# TransducerStuff.net
KiCad netlist of a schematic drawn in EAGLE
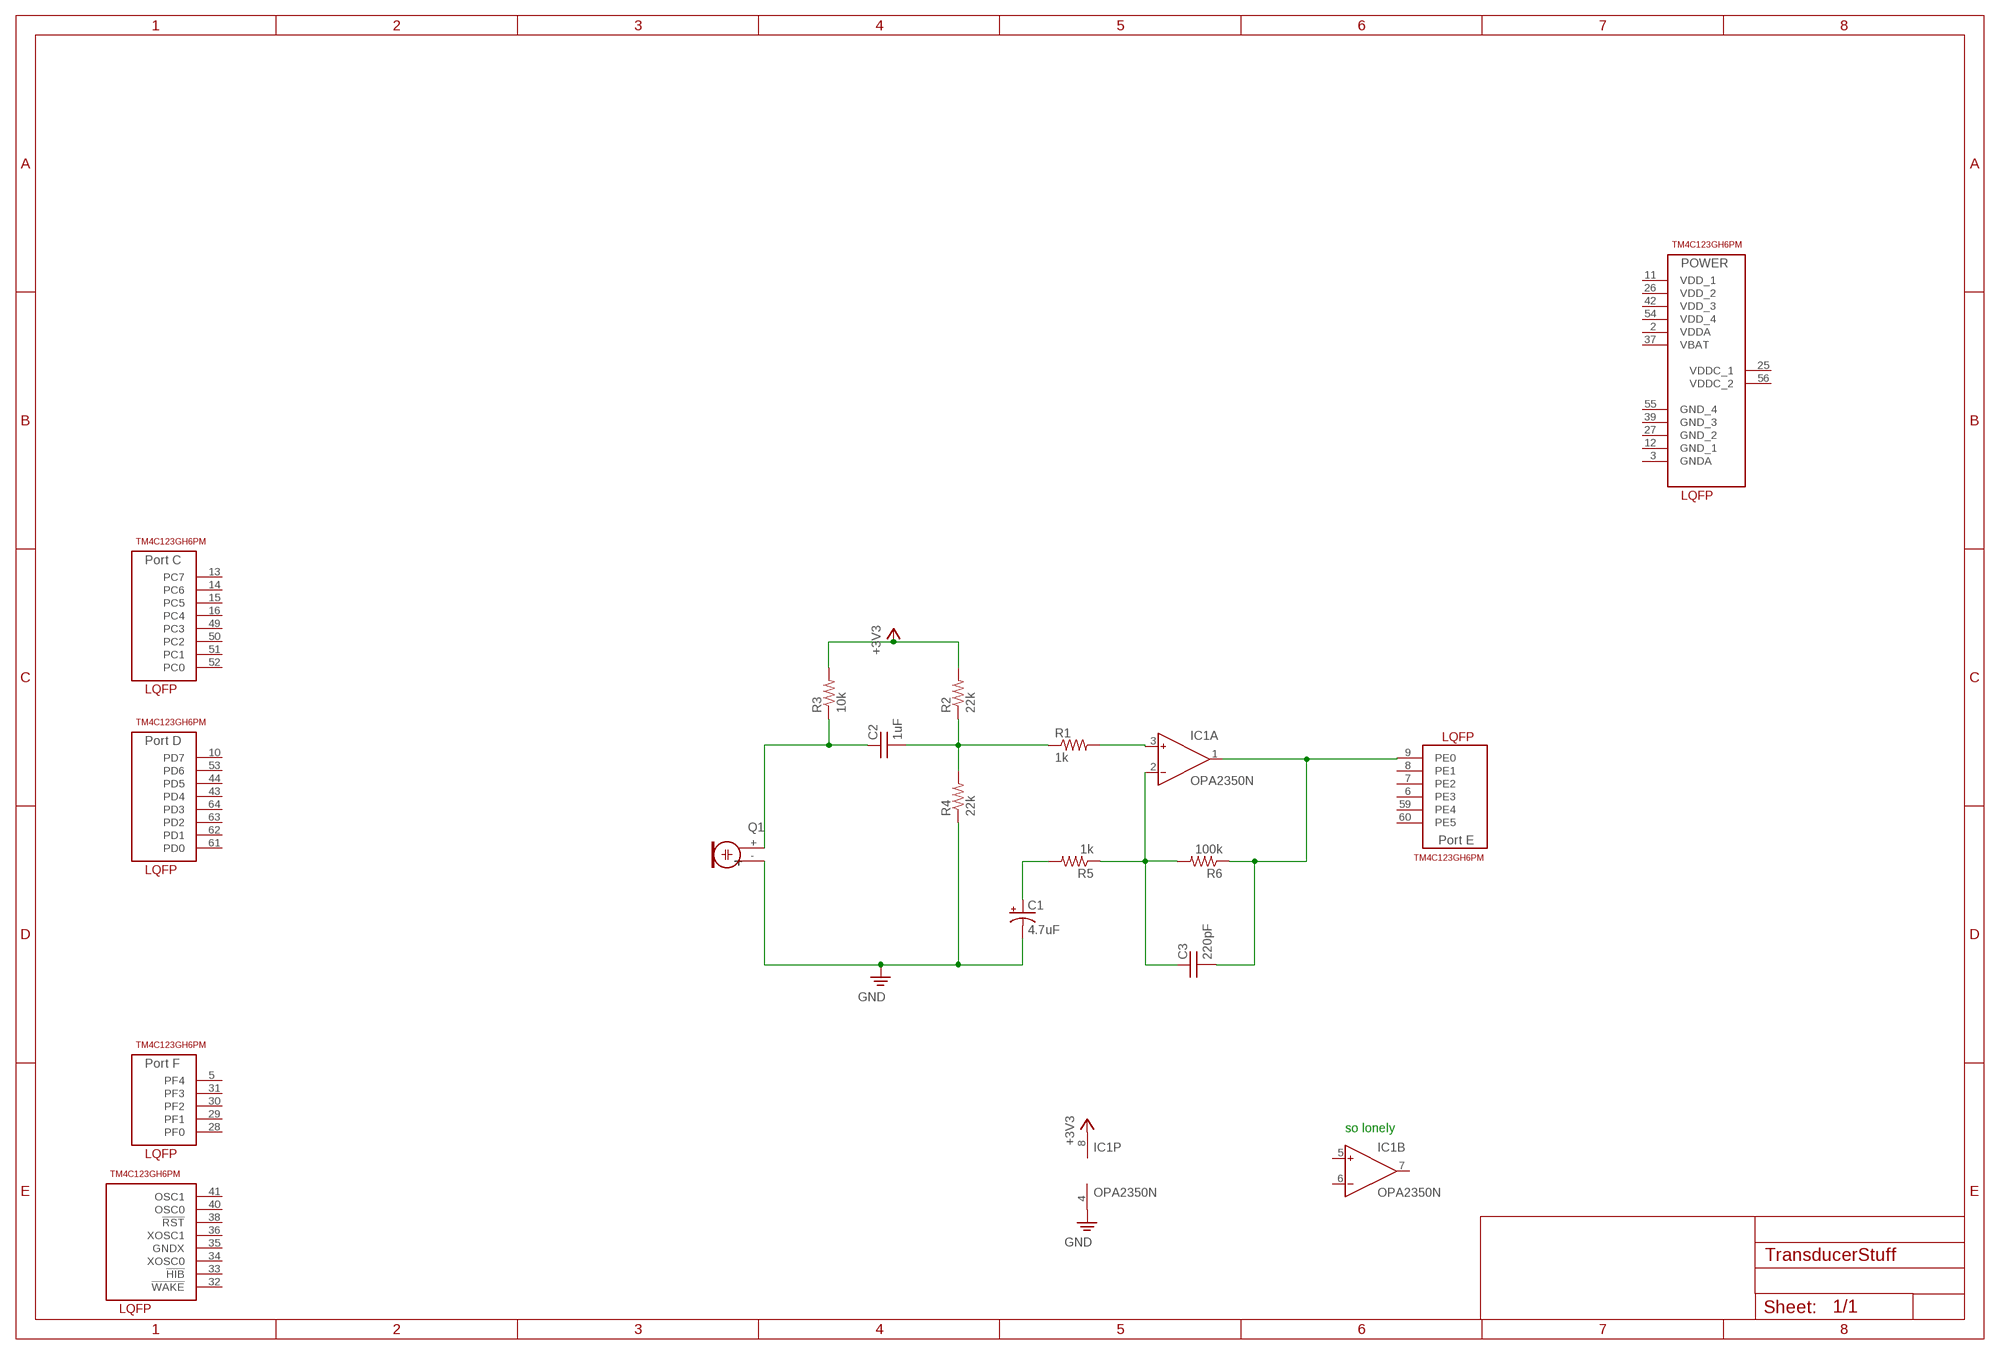
[diagram p0: schematic, sheet 1, part 1 of 2]
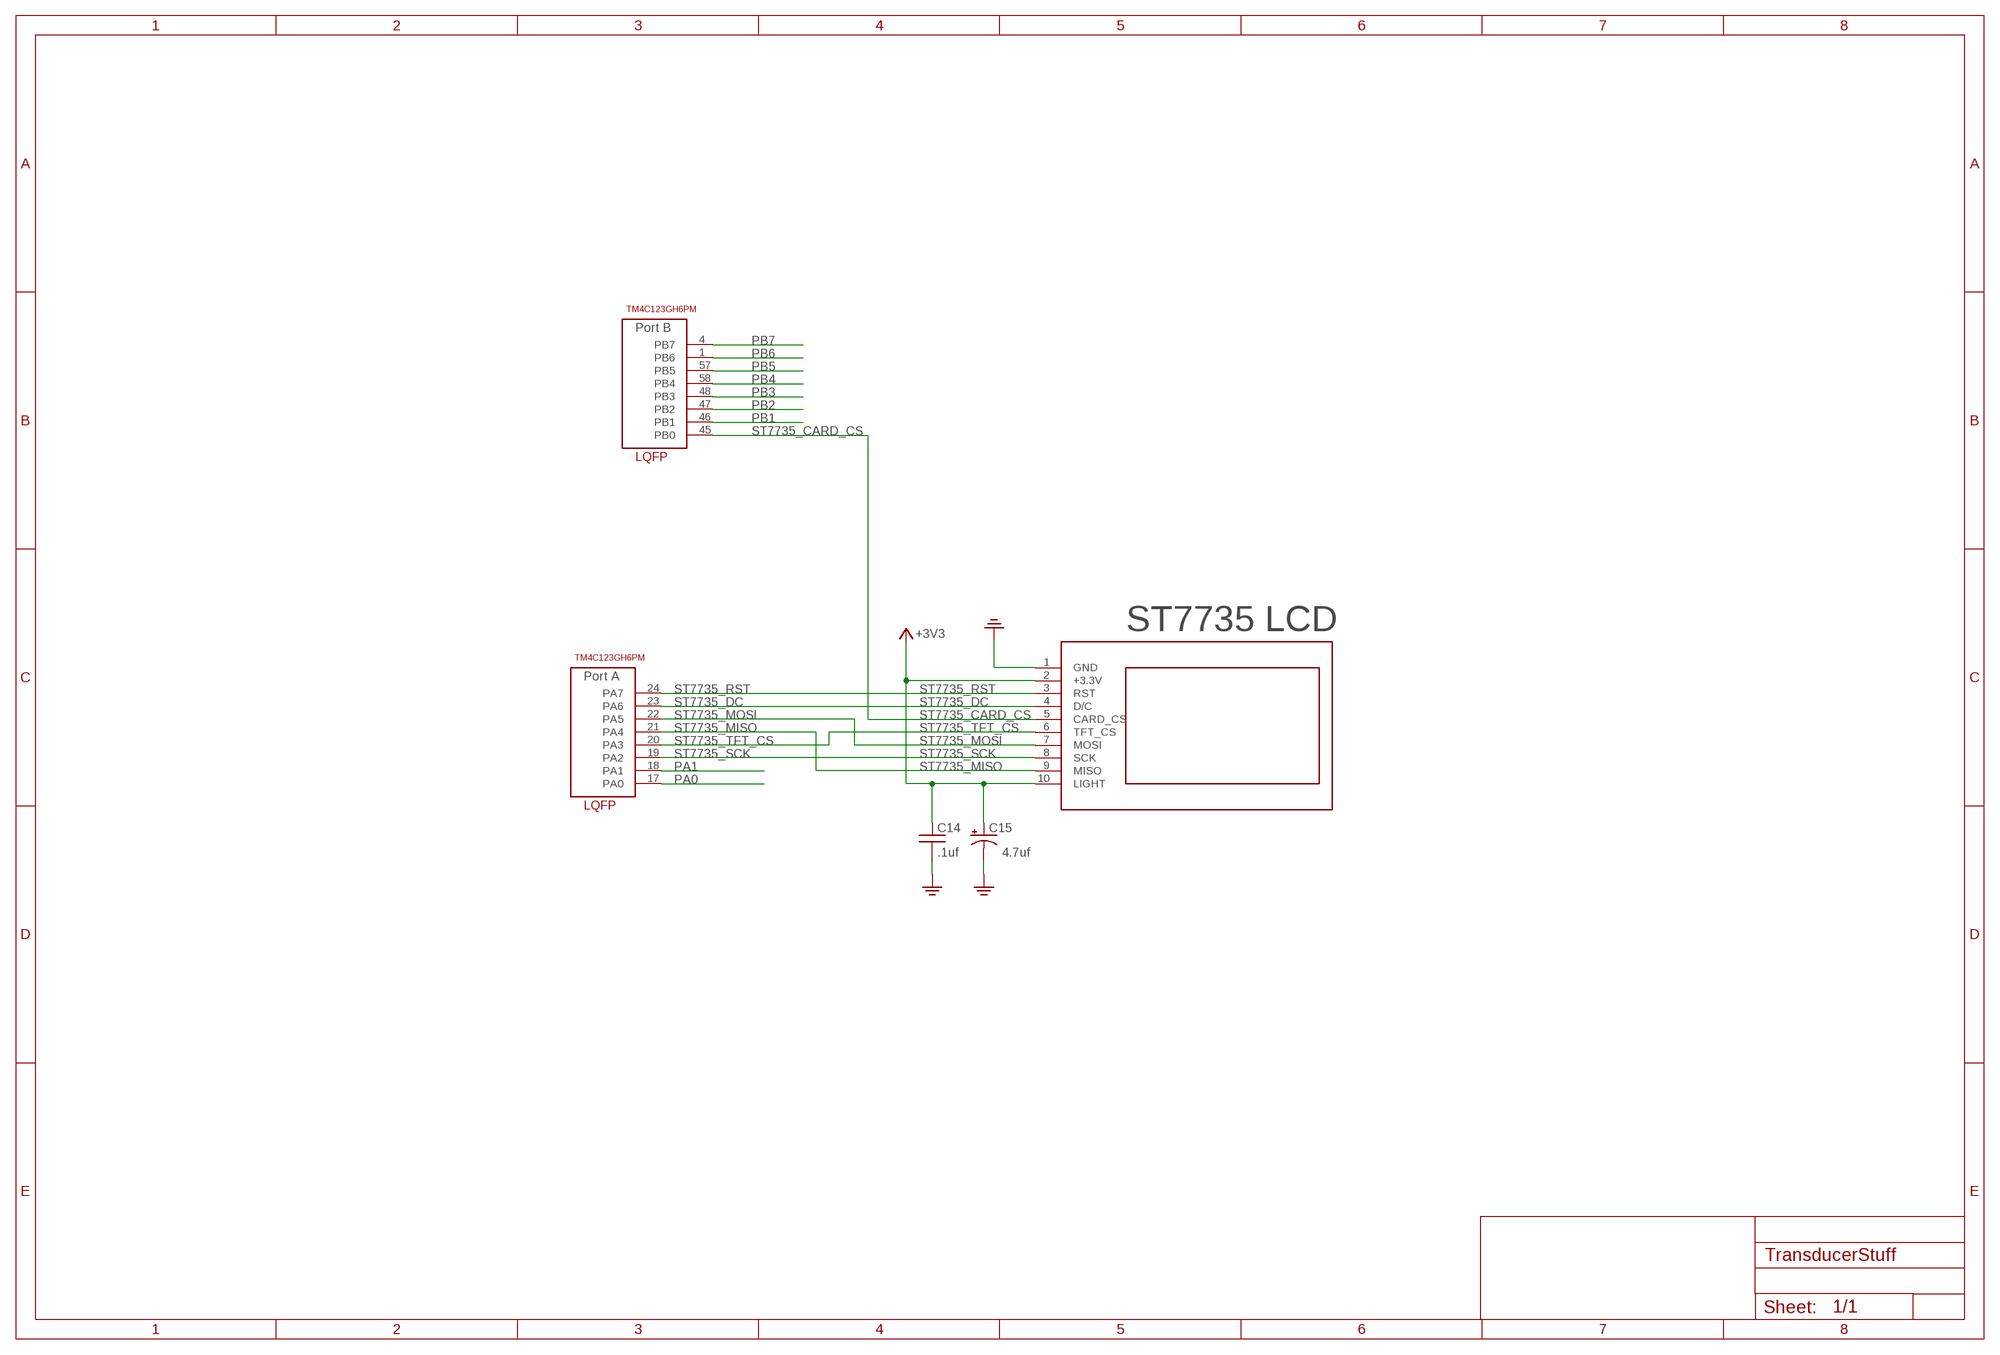
[diagram p1: schematic, sheet 1, part 2 of 2]

(export (version "E")
  (design (tool "Eeschema 10.0.6"))
  (components
    (comp (ref "C1")
      (value "4.7uF")
      (footprint "eagle-import:CAP200MILPOLARIZED")
      (libsource (lib "eagle-import") (part "CAPACITOR_POLARIZEDE5-6"))
    )
    (comp (ref "C2")
      (value "1uF")
      (footprint "eagle-import:CAP200MIL")
      (libsource (lib "eagle-import") (part "CAPACITOR050-024X044"))
    )
    (comp (ref "C3")
      (value "220pF")
      (footprint "eagle-import:CAP200MIL")
      (libsource (lib "eagle-import") (part "CAPACITOR050-024X044"))
    )
    (comp (ref "C14")
      (value ".1uf")
      (footprint "eagle-import:CAP200MIL")
      (libsource (lib "eagle-import") (part "CAPACITOR050-024X044"))
    )
    (comp (ref "C15")
      (value "4.7uf")
      (footprint "eagle-import:CAP200MILPOLARIZED")
      (libsource (lib "eagle-import") (part "CAPACITOR_POLARIZEDE5-6"))
    )
    (comp (ref "IC1")
      (value "OPA2350N")
      (footprint "eagle-import:DIL08")
      (libsource (lib "eagle-import") (part "OPA2350N"))
    )
    (comp (ref "Q1")
      (value "ELECTRET")
      (footprint "eagle-import:9.7ELECTRET")
      (libsource (lib "eagle-import") (part "ELECTRET"))
    )
    (comp (ref "R1")
      (value "1k")
      (footprint "eagle-import:RES400MIL")
      (libsource (lib "eagle-import") (part "RESISTOR0309/10"))
    )
    (comp (ref "R2")
      (value "22k")
      (footprint "eagle-import:RES400MIL")
      (libsource (lib "eagle-import") (part "RESISTOR0309/10"))
    )
    (comp (ref "R3")
      (value "10k")
      (footprint "eagle-import:RES400MIL")
      (libsource (lib "eagle-import") (part "RESISTOR0309/10"))
    )
    (comp (ref "R4")
      (value "22k")
      (footprint "eagle-import:RES400MIL")
      (libsource (lib "eagle-import") (part "RESISTOR0309/10"))
    )
    (comp (ref "R5")
      (value "1k")
      (footprint "eagle-import:RES400MIL")
      (libsource (lib "eagle-import") (part "RESISTOR0309/10"))
    )
    (comp (ref "R6")
      (value "100k")
      (footprint "eagle-import:RES400MIL")
      (libsource (lib "eagle-import") (part "RESISTOR0309/10"))
    )
    (comp (ref "U$1")
      (value "TM4C123GH6PM")
      (footprint "eagle-import:QFP50P1200X1200X160-64N")
      (libsource (lib "eagle-import") (part "TM4C123GH6PM"))
    )
    (comp (ref "U$2")
      (value "TM4C123GH6PM")
      (footprint "eagle-import:QFP50P1200X1200X160-64N")
      (libsource (lib "eagle-import") (part "TM4C123GH6PM"))
    )
    (comp (ref "U$3")
      (value "TM4C123GH6PM")
      (footprint "eagle-import:QFP50P1200X1200X160-64N")
      (libsource (lib "eagle-import") (part "TM4C123GH6PM"))
    )
    (comp (ref "U$4")
      (value "TM4C123GH6PM")
      (footprint "eagle-import:QFP50P1200X1200X160-64N")
      (libsource (lib "eagle-import") (part "TM4C123GH6PM"))
    )
    (comp (ref "U$5")
      (value "TM4C123GH6PM")
      (footprint "eagle-import:QFP50P1200X1200X160-64N")
      (libsource (lib "eagle-import") (part "TM4C123GH6PM"))
    )
    (comp (ref "U$6")
      (value "TM4C123GH6PM")
      (footprint "eagle-import:QFP50P1200X1200X160-64N")
      (libsource (lib "eagle-import") (part "TM4C123GH6PM"))
    )
    (comp (ref "U$7")
      (value "TM4C123GH6PM")
      (footprint "eagle-import:QFP50P1200X1200X160-64N")
      (libsource (lib "eagle-import") (part "TM4C123GH6PM"))
    )
    (comp (ref "U$8")
      (value "TM4C123GH6PM")
      (footprint "eagle-import:QFP50P1200X1200X160-64N")
      (libsource (lib "eagle-import") (part "TM4C123GH6PM"))
    )
    (comp (ref "U$10")
      (value "ST7735")
      (footprint "eagle-import:ST7735")
      (libsource (lib "eagle-import") (part "ST7735"))
    )
  )
  (nets
    (net (code "1") (name "+3V3") (class "Default")
      (node (ref "C14") (pin "1") (pinfunction "1_1") (pintype "passive"))
      (node (ref "C15") (pin "+") (pinfunction "+_+") (pintype "passive"))
      (node (ref "IC1") (pin "8") (pinfunction "V+_8") (pintype "power_in"))
      (node (ref "R2") (pin "2") (pinfunction "2_2") (pintype "passive"))
      (node (ref "R3") (pin "2") (pinfunction "2_2") (pintype "passive"))
      (node (ref "U$10") (pin "10") (pinfunction "LIGHT_10") (pintype "bidirectional"))
      (node (ref "U$10") (pin "2") (pinfunction "+3.3V_2") (pintype "bidirectional"))
    )
    (net (code "2") (name "/PA0") (class "Default")
      (node (ref "U$2") (pin "17") (pinfunction "PA0_17") (pintype "bidirectional"))
    )
    (net (code "3") (name "/PA1") (class "Default")
      (node (ref "U$2") (pin "18") (pinfunction "PA1_18") (pintype "bidirectional"))
    )
    (net (code "4") (name "/PB1") (class "Default")
      (node (ref "U$3") (pin "46") (pinfunction "PB1_46") (pintype "bidirectional"))
    )
    (net (code "5") (name "/PB2") (class "Default")
      (node (ref "U$3") (pin "47") (pinfunction "PB2_47") (pintype "bidirectional"))
    )
    (net (code "6") (name "/PB3") (class "Default")
      (node (ref "U$3") (pin "48") (pinfunction "PB3_48") (pintype "bidirectional"))
    )
    (net (code "7") (name "/PB4") (class "Default")
      (node (ref "U$3") (pin "58") (pinfunction "PB4_58") (pintype "bidirectional"))
    )
    (net (code "8") (name "/PB5") (class "Default")
      (node (ref "U$3") (pin "57") (pinfunction "PB5_57") (pintype "bidirectional"))
    )
    (net (code "9") (name "/PB6") (class "Default")
      (node (ref "U$3") (pin "1") (pinfunction "PB6_1") (pintype "bidirectional"))
    )
    (net (code "10") (name "/PB7") (class "Default")
      (node (ref "U$3") (pin "4") (pinfunction "PB7_4") (pintype "bidirectional"))
    )
    (net (code "11") (name "/ST7735_CARD_CS") (class "Default")
      (node (ref "U$10") (pin "5") (pinfunction "CARD_CS_5") (pintype "bidirectional"))
      (node (ref "U$3") (pin "45") (pinfunction "PB0_45") (pintype "bidirectional"))
    )
    (net (code "12") (name "/ST7735_DC") (class "Default")
      (node (ref "U$10") (pin "4") (pinfunction "D/C_4") (pintype "bidirectional"))
      (node (ref "U$2") (pin "23") (pinfunction "PA6_23") (pintype "bidirectional"))
    )
    (net (code "13") (name "/ST7735_MISO") (class "Default")
      (node (ref "U$10") (pin "9") (pinfunction "MISO_9") (pintype "bidirectional"))
      (node (ref "U$2") (pin "21") (pinfunction "PA4_21") (pintype "bidirectional"))
    )
    (net (code "14") (name "/ST7735_MOSI") (class "Default")
      (node (ref "U$10") (pin "7") (pinfunction "MOSI_7") (pintype "bidirectional"))
      (node (ref "U$2") (pin "22") (pinfunction "PA5_22") (pintype "bidirectional"))
    )
    (net (code "15") (name "/ST7735_RST") (class "Default")
      (node (ref "U$10") (pin "3") (pinfunction "RST_3") (pintype "bidirectional"))
      (node (ref "U$2") (pin "24") (pinfunction "PA7_24") (pintype "bidirectional"))
    )
    (net (code "16") (name "/ST7735_SCK") (class "Default")
      (node (ref "U$10") (pin "8") (pinfunction "SCK_8") (pintype "bidirectional"))
      (node (ref "U$2") (pin "19") (pinfunction "PA2_19") (pintype "bidirectional"))
    )
    (net (code "17") (name "/ST7735_TFT_CS") (class "Default")
      (node (ref "U$10") (pin "6") (pinfunction "TFT_CS_6") (pintype "bidirectional"))
      (node (ref "U$2") (pin "20") (pinfunction "PA3_20") (pintype "bidirectional"))
    )
    (net (code "18") (name "GND") (class "Default")
      (node (ref "C1") (pin "-") (pinfunction "-_-") (pintype "passive"))
      (node (ref "C14") (pin "2") (pinfunction "2_2") (pintype "passive"))
      (node (ref "C15") (pin "-") (pinfunction "-_-") (pintype "passive"))
      (node (ref "IC1") (pin "4") (pinfunction "V-_4") (pintype "power_in"))
      (node (ref "Q1") (pin "-") (pinfunction "1_-") (pintype "passive"))
      (node (ref "R4") (pin "1") (pinfunction "1_1") (pintype "passive"))
      (node (ref "U$10") (pin "1") (pinfunction "GND_1") (pintype "bidirectional"))
    )
    (net (code "19") (name "Net-(C1-Pad+)") (class "Default")
      (node (ref "C1") (pin "+") (pinfunction "+_+") (pintype "passive"))
      (node (ref "R5") (pin "2") (pinfunction "2_2") (pintype "passive"))
    )
    (net (code "20") (name "Net-(C2-Pad2)") (class "Default")
      (node (ref "C2") (pin "2") (pinfunction "2_2") (pintype "passive"))
      (node (ref "R1") (pin "1") (pinfunction "1_1") (pintype "passive"))
      (node (ref "R2") (pin "1") (pinfunction "1_1") (pintype "passive"))
      (node (ref "R4") (pin "2") (pinfunction "2_2") (pintype "passive"))
    )
    (net (code "21") (name "Net-(IC1A-IN+)") (class "Default")
      (node (ref "IC1") (pin "3") (pinfunction "IN+_3") (pintype "input"))
      (node (ref "R1") (pin "2") (pinfunction "2_2") (pintype "passive"))
    )
    (net (code "22") (name "Net-(IC1A-IN-)") (class "Default")
      (node (ref "C3") (pin "1") (pinfunction "1_1") (pintype "passive"))
      (node (ref "IC1") (pin "2") (pinfunction "IN-_2") (pintype "input"))
      (node (ref "R5") (pin "1") (pinfunction "1_1") (pintype "passive"))
      (node (ref "R6") (pin "2") (pinfunction "2_2") (pintype "passive"))
    )
    (net (code "23") (name "Net-(IC1A-OUT)") (class "Default")
      (node (ref "C3") (pin "2") (pinfunction "2_2") (pintype "passive"))
      (node (ref "IC1") (pin "1") (pinfunction "OUT_1") (pintype "output"))
      (node (ref "R6") (pin "1") (pinfunction "1_1") (pintype "passive"))
      (node (ref "U$6") (pin "9") (pinfunction "PE0_9") (pintype "bidirectional"))
    )
    (net (code "24") (name "Net-(Q1-2)") (class "Default")
      (node (ref "C2") (pin "1") (pinfunction "1_1") (pintype "passive"))
      (node (ref "Q1") (pin "+") (pinfunction "2_+") (pintype "passive"))
      (node (ref "R3") (pin "1") (pinfunction "1_1") (pintype "passive"))
    )
    (net (code "25") (name "unconnected-(IC1B-IN+-Pad5)") (class "Default")
      (node (ref "IC1") (pin "5") (pinfunction "IN+_5") (pintype "input"))
    )
    (net (code "26") (name "unconnected-(IC1B-IN--Pad6)") (class "Default")
      (node (ref "IC1") (pin "6") (pinfunction "IN-_6") (pintype "input"))
    )
    (net (code "27") (name "unconnected-(IC1B-OUT-Pad7)") (class "Default")
      (node (ref "IC1") (pin "7") (pinfunction "OUT_7") (pintype "output"))
    )
    (net (code "28") (name "unconnected-(U$1G-GNDX-Pad35)") (class "Default")
      (node (ref "U$1") (pin "35") (pinfunction "GNDX_35") (pintype "bidirectional"))
    )
    (net (code "29") (name "unconnected-(U$1G-OSC0-Pad40)") (class "Default")
      (node (ref "U$1") (pin "40") (pinfunction "OSC0_40") (pintype "bidirectional"))
    )
    (net (code "30") (name "unconnected-(U$1G-OSC1-Pad41)") (class "Default")
      (node (ref "U$1") (pin "41") (pinfunction "OSC1_41") (pintype "bidirectional"))
    )
    (net (code "31") (name "unconnected-(U$1G-XOSC0-Pad34)") (class "Default")
      (node (ref "U$1") (pin "34") (pinfunction "XOSC0_34") (pintype "bidirectional"))
    )
    (net (code "32") (name "unconnected-(U$1G-XOSC1-Pad36)") (class "Default")
      (node (ref "U$1") (pin "36") (pinfunction "XOSC1_36") (pintype "bidirectional"))
    )
    (net (code "33") (name "unconnected-(U$1G-~{HIB}-Pad33)") (class "Default")
      (node (ref "U$1") (pin "33") (pinfunction "~{HIB}_33") (pintype "bidirectional"))
    )
    (net (code "34") (name "unconnected-(U$1G-~{RST}-Pad38)") (class "Default")
      (node (ref "U$1") (pin "38") (pinfunction "~{RST}_38") (pintype "bidirectional"))
    )
    (net (code "35") (name "unconnected-(U$1G-~{WAKE}-Pad32)") (class "Default")
      (node (ref "U$1") (pin "32") (pinfunction "~{WAKE}_32") (pintype "bidirectional"))
    )
    (net (code "36") (name "unconnected-(U$4C-PC0-Pad52)") (class "Default")
      (node (ref "U$4") (pin "52") (pinfunction "PC0_52") (pintype "bidirectional"))
    )
    (net (code "37") (name "unconnected-(U$4C-PC1-Pad51)") (class "Default")
      (node (ref "U$4") (pin "51") (pinfunction "PC1_51") (pintype "bidirectional"))
    )
    (net (code "38") (name "unconnected-(U$4C-PC2-Pad50)") (class "Default")
      (node (ref "U$4") (pin "50") (pinfunction "PC2_50") (pintype "bidirectional"))
    )
    (net (code "39") (name "unconnected-(U$4C-PC3-Pad49)") (class "Default")
      (node (ref "U$4") (pin "49") (pinfunction "PC3_49") (pintype "bidirectional"))
    )
    (net (code "40") (name "unconnected-(U$4C-PC4-Pad16)") (class "Default")
      (node (ref "U$4") (pin "16") (pinfunction "PC4_16") (pintype "bidirectional"))
    )
    (net (code "41") (name "unconnected-(U$4C-PC5-Pad15)") (class "Default")
      (node (ref "U$4") (pin "15") (pinfunction "PC5_15") (pintype "bidirectional"))
    )
    (net (code "42") (name "unconnected-(U$4C-PC6-Pad14)") (class "Default")
      (node (ref "U$4") (pin "14") (pinfunction "PC6_14") (pintype "bidirectional"))
    )
    (net (code "43") (name "unconnected-(U$4C-PC7-Pad13)") (class "Default")
      (node (ref "U$4") (pin "13") (pinfunction "PC7_13") (pintype "bidirectional"))
    )
    (net (code "44") (name "unconnected-(U$5D-PD0-Pad61)") (class "Default")
      (node (ref "U$5") (pin "61") (pinfunction "PD0_61") (pintype "bidirectional"))
    )
    (net (code "45") (name "unconnected-(U$5D-PD1-Pad62)") (class "Default")
      (node (ref "U$5") (pin "62") (pinfunction "PD1_62") (pintype "bidirectional"))
    )
    (net (code "46") (name "unconnected-(U$5D-PD2-Pad63)") (class "Default")
      (node (ref "U$5") (pin "63") (pinfunction "PD2_63") (pintype "bidirectional"))
    )
    (net (code "47") (name "unconnected-(U$5D-PD3-Pad64)") (class "Default")
      (node (ref "U$5") (pin "64") (pinfunction "PD3_64") (pintype "bidirectional"))
    )
    (net (code "48") (name "unconnected-(U$5D-PD4-Pad43)") (class "Default")
      (node (ref "U$5") (pin "43") (pinfunction "PD4_43") (pintype "bidirectional"))
    )
    (net (code "49") (name "unconnected-(U$5D-PD5-Pad44)") (class "Default")
      (node (ref "U$5") (pin "44") (pinfunction "PD5_44") (pintype "bidirectional"))
    )
    (net (code "50") (name "unconnected-(U$5D-PD6-Pad53)") (class "Default")
      (node (ref "U$5") (pin "53") (pinfunction "PD6_53") (pintype "bidirectional"))
    )
    (net (code "51") (name "unconnected-(U$5D-PD7-Pad10)") (class "Default")
      (node (ref "U$5") (pin "10") (pinfunction "PD7_10") (pintype "bidirectional"))
    )
    (net (code "52") (name "unconnected-(U$6E-PE1-Pad8)") (class "Default")
      (node (ref "U$6") (pin "8") (pinfunction "PE1_8") (pintype "bidirectional"))
    )
    (net (code "53") (name "unconnected-(U$6E-PE2-Pad7)") (class "Default")
      (node (ref "U$6") (pin "7") (pinfunction "PE2_7") (pintype "bidirectional"))
    )
    (net (code "54") (name "unconnected-(U$6E-PE3-Pad6)") (class "Default")
      (node (ref "U$6") (pin "6") (pinfunction "PE3_6") (pintype "bidirectional"))
    )
    (net (code "55") (name "unconnected-(U$6E-PE4-Pad59)") (class "Default")
      (node (ref "U$6") (pin "59") (pinfunction "PE4_59") (pintype "bidirectional"))
    )
    (net (code "56") (name "unconnected-(U$6E-PE5-Pad60)") (class "Default")
      (node (ref "U$6") (pin "60") (pinfunction "PE5_60") (pintype "bidirectional"))
    )
    (net (code "57") (name "unconnected-(U$7F-PF0-Pad28)") (class "Default")
      (node (ref "U$7") (pin "28") (pinfunction "PF0_28") (pintype "bidirectional"))
    )
    (net (code "58") (name "unconnected-(U$7F-PF1-Pad29)") (class "Default")
      (node (ref "U$7") (pin "29") (pinfunction "PF1_29") (pintype "bidirectional"))
    )
    (net (code "59") (name "unconnected-(U$7F-PF2-Pad30)") (class "Default")
      (node (ref "U$7") (pin "30") (pinfunction "PF2_30") (pintype "bidirectional"))
    )
    (net (code "60") (name "unconnected-(U$7F-PF3-Pad31)") (class "Default")
      (node (ref "U$7") (pin "31") (pinfunction "PF3_31") (pintype "bidirectional"))
    )
    (net (code "61") (name "unconnected-(U$7F-PF4-Pad5)") (class "Default")
      (node (ref "U$7") (pin "5") (pinfunction "PF4_5") (pintype "bidirectional"))
    )
    (net (code "62") (name "unconnected-(U$8H-GNDA-Pad3)") (class "Default")
      (node (ref "U$8") (pin "3") (pinfunction "GNDA_3") (pintype "bidirectional"))
    )
    (net (code "63") (name "unconnected-(U$8H-GND_1-Pad12)") (class "Default")
      (node (ref "U$8") (pin "12") (pinfunction "GND_1_12") (pintype "bidirectional"))
    )
    (net (code "64") (name "unconnected-(U$8H-GND_2-Pad27)") (class "Default")
      (node (ref "U$8") (pin "27") (pinfunction "GND_2_27") (pintype "bidirectional"))
    )
    (net (code "65") (name "unconnected-(U$8H-GND_3-Pad39)") (class "Default")
      (node (ref "U$8") (pin "39") (pinfunction "GND_3_39") (pintype "bidirectional"))
    )
    (net (code "66") (name "unconnected-(U$8H-GND_4-Pad55)") (class "Default")
      (node (ref "U$8") (pin "55") (pinfunction "GND_4_55") (pintype "bidirectional"))
    )
    (net (code "67") (name "unconnected-(U$8H-VBAT-Pad37)") (class "Default")
      (node (ref "U$8") (pin "37") (pinfunction "VBAT_37") (pintype "bidirectional"))
    )
    (net (code "68") (name "unconnected-(U$8H-VDDA-Pad2)") (class "Default")
      (node (ref "U$8") (pin "2") (pinfunction "VDDA_2") (pintype "bidirectional"))
    )
    (net (code "69") (name "unconnected-(U$8H-VDDC_1-Pad25)") (class "Default")
      (node (ref "U$8") (pin "25") (pinfunction "VDDC_1_25") (pintype "bidirectional"))
    )
    (net (code "70") (name "unconnected-(U$8H-VDDC_2-Pad56)") (class "Default")
      (node (ref "U$8") (pin "56") (pinfunction "VDDC_2_56") (pintype "bidirectional"))
    )
    (net (code "71") (name "unconnected-(U$8H-VDD_1-Pad11)") (class "Default")
      (node (ref "U$8") (pin "11") (pinfunction "VDD_1_11") (pintype "bidirectional"))
    )
    (net (code "72") (name "unconnected-(U$8H-VDD_2-Pad26)") (class "Default")
      (node (ref "U$8") (pin "26") (pinfunction "VDD_2_26") (pintype "bidirectional"))
    )
    (net (code "73") (name "unconnected-(U$8H-VDD_3-Pad42)") (class "Default")
      (node (ref "U$8") (pin "42") (pinfunction "VDD_3_42") (pintype "bidirectional"))
    )
    (net (code "74") (name "unconnected-(U$8H-VDD_4-Pad54)") (class "Default")
      (node (ref "U$8") (pin "54") (pinfunction "VDD_4_54") (pintype "bidirectional"))
    )
  )
)
